# nodeBoard.net
KiCad netlist of a schematic drawn in EAGLE
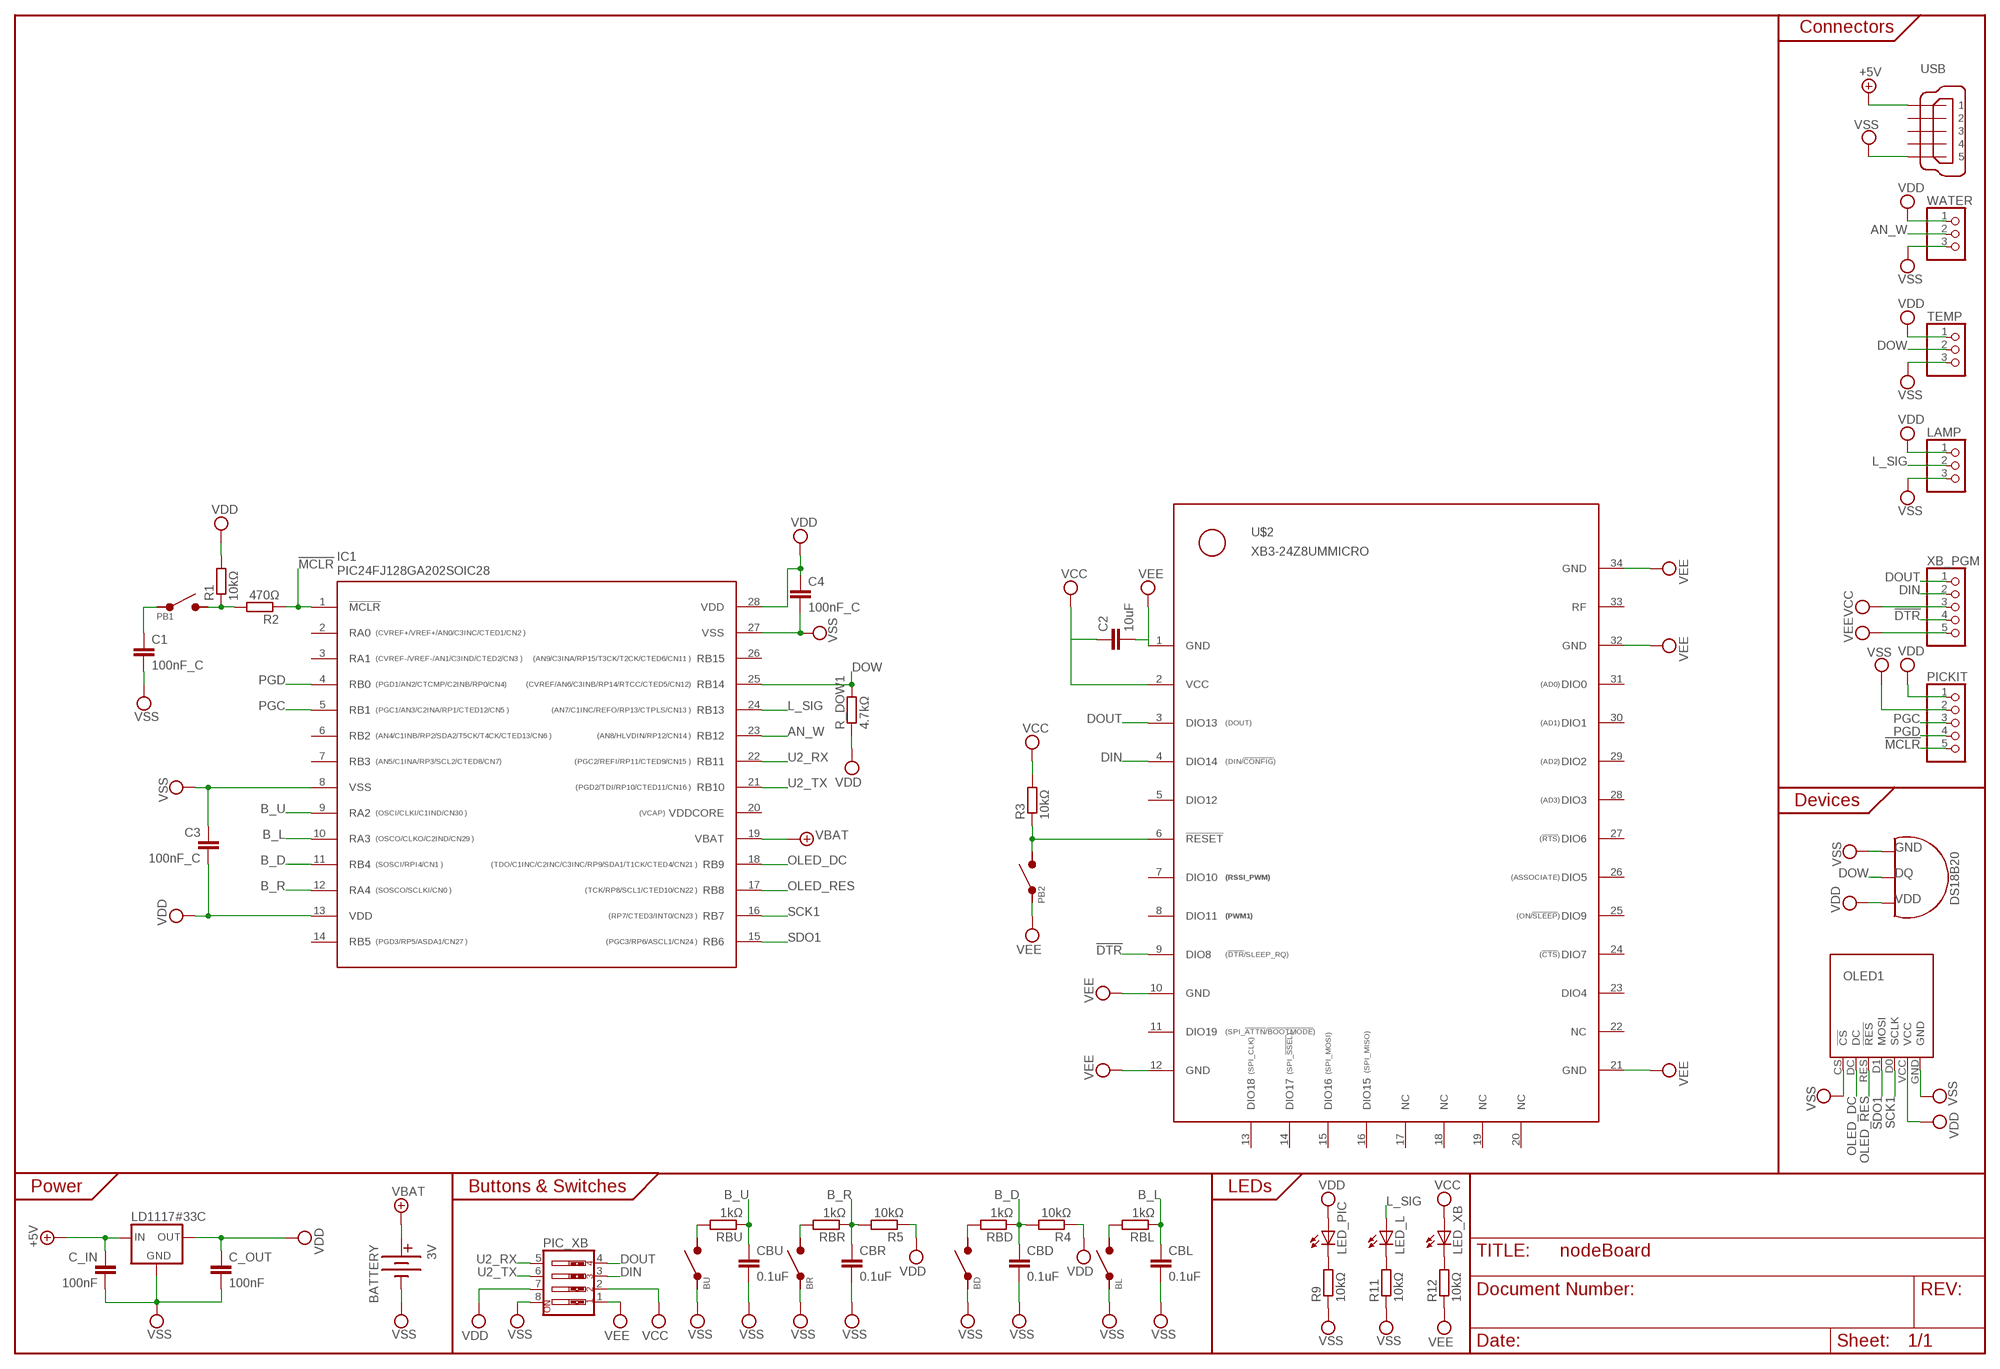
[diagram p0: schematic, sheet 1]

(export (version "E")
  (design (tool "Eeschema 10.0.6"))
  (components
    (comp (ref "3V")
      (value "BATTERY")
      (footprint "eagle-import:20MM_CELLHOLDER")
      (libsource (lib "eagle-import") (part "BATTERY"))
    )
    (comp (ref "BD")
      (value "PUSHBUTTON_4LEG_SMD")
      (footprint "eagle-import:TACTILE_SWITCH_SMD_6.2MM_BROWN")
      (libsource (lib "eagle-import") (part "PUSHBUTTON_4LEG_SMD"))
    )
    (comp (ref "BL")
      (value "PUSHBUTTON_4LEG_SMD")
      (footprint "eagle-import:TACTILE_SWITCH_SMD_6.2MM_BROWN")
      (libsource (lib "eagle-import") (part "PUSHBUTTON_4LEG_SMD"))
    )
    (comp (ref "BR")
      (value "PUSHBUTTON_4LEG_SMD")
      (footprint "eagle-import:TACTILE_SWITCH_SMD_6.2MM_BROWN")
      (libsource (lib "eagle-import") (part "PUSHBUTTON_4LEG_SMD"))
    )
    (comp (ref "BU")
      (value "PUSHBUTTON_4LEG_SMD")
      (footprint "eagle-import:TACTILE_SWITCH_SMD_6.2MM_BROWN")
      (libsource (lib "eagle-import") (part "PUSHBUTTON_4LEG_SMD"))
    )
    (comp (ref "C1")
      (value "100nF_C")
      (footprint "eagle-import:C0805")
      (libsource (lib "eagle-import") (part "C-EUC0805"))
    )
    (comp (ref "C2")
      (value "10uF")
      (footprint "eagle-import:C0805")
      (libsource (lib "eagle-import") (part "C-EUC0805"))
    )
    (comp (ref "C3")
      (value "100nF_C")
      (footprint "eagle-import:C0805")
      (libsource (lib "eagle-import") (part "C-EUC0805"))
    )
    (comp (ref "C4")
      (value "100nF_C")
      (footprint "eagle-import:C0805")
      (libsource (lib "eagle-import") (part "C-EUC0805"))
    )
    (comp (ref "CBD")
      (value "0.1uF")
      (footprint "eagle-import:C0805")
      (libsource (lib "eagle-import") (part "C-EUC0805"))
    )
    (comp (ref "CBL")
      (value "0.1uF")
      (footprint "eagle-import:C0805")
      (libsource (lib "eagle-import") (part "C-EUC0805"))
    )
    (comp (ref "CBR")
      (value "0.1uF")
      (footprint "eagle-import:C0805")
      (libsource (lib "eagle-import") (part "C-EUC0805"))
    )
    (comp (ref "CBU")
      (value "0.1uF")
      (footprint "eagle-import:C0805")
      (libsource (lib "eagle-import") (part "C-EUC0805"))
    )
    (comp (ref "C_IN")
      (value "100nF")
      (footprint "eagle-import:C0805")
      (libsource (lib "eagle-import") (part "C-EUC0805"))
    )
    (comp (ref "C_OUT")
      (value "100nF")
      (footprint "eagle-import:C0805")
      (libsource (lib "eagle-import") (part "C-EUC0805"))
    )
    (comp (ref "IC1")
      (value "PIC24FJ128GA202SOIC28")
      (footprint "eagle-import:SOIC28L")
      (libsource (lib "eagle-import") (part "PIC24FJ128GA202SOIC28"))
    )
    (comp (ref "LAMP")
      (value "PINHD-1X3")
      (footprint "eagle-import:1X03")
      (libsource (lib "eagle-import") (part "PINHD-1X3"))
    )
    (comp (ref "LED_L")
      (value "LEDCHIPLED_0805")
      (footprint "eagle-import:CHIPLED_0805")
      (libsource (lib "eagle-import") (part "LEDCHIPLED_0805"))
    )
    (comp (ref "LED_PIC")
      (value "LEDCHIPLED_0805")
      (footprint "eagle-import:CHIPLED_0805")
      (libsource (lib "eagle-import") (part "LEDCHIPLED_0805"))
    )
    (comp (ref "LED_XB")
      (value "LEDCHIPLED_0805")
      (footprint "eagle-import:CHIPLED_0805")
      (libsource (lib "eagle-import") (part "LEDCHIPLED_0805"))
    )
    (comp (ref "OLED1")
      (value "OLED_7PIN_SPI")
      (footprint "eagle-import:OLED_7PIN")
      (libsource (lib "eagle-import") (part "OLED_7PIN_SPI"))
    )
    (comp (ref "PB1")
      (value "PUSHBUTTON_2LEG")
      (footprint "eagle-import:PUSHBUTTON_6X3.5MM")
      (libsource (lib "eagle-import") (part "PUSHBUTTON_2LEG"))
    )
    (comp (ref "PB2")
      (value "PUSHBUTTON_2LEG")
      (footprint "eagle-import:PUSHBUTTON_6X3.5MM")
      (libsource (lib "eagle-import") (part "PUSHBUTTON_2LEG"))
    )
    (comp (ref "PICKIT")
      (value "PINHD-1X5")
      (footprint "eagle-import:1X05")
      (libsource (lib "eagle-import") (part "PINHD-1X5"))
    )
    (comp (ref "PIC_XB")
      (value "SW_DIP-4")
      (footprint "eagle-import:EDG-04")
      (libsource (lib "eagle-import") (part "SW_DIP-4"))
    )
    (comp (ref "R1")
      (value "10kΩ")
      (footprint "eagle-import:R0805")
      (libsource (lib "eagle-import") (part "R-EU_R0805"))
    )
    (comp (ref "R2")
      (value "470Ω")
      (footprint "eagle-import:R0805")
      (libsource (lib "eagle-import") (part "R-EU_R0805"))
    )
    (comp (ref "R3")
      (value "10kΩ")
      (footprint "eagle-import:R0805")
      (libsource (lib "eagle-import") (part "R-EU_R0805"))
    )
    (comp (ref "R4")
      (value "10kΩ")
      (footprint "eagle-import:R0805")
      (libsource (lib "eagle-import") (part "R-EU_R0805"))
    )
    (comp (ref "R5")
      (value "10kΩ")
      (footprint "eagle-import:R0805")
      (libsource (lib "eagle-import") (part "R-EU_R0805"))
    )
    (comp (ref "R9")
      (value "10kΩ")
      (footprint "eagle-import:R0805")
      (libsource (lib "eagle-import") (part "R-EU_R0805"))
    )
    (comp (ref "R11")
      (value "10kΩ")
      (footprint "eagle-import:R0805")
      (libsource (lib "eagle-import") (part "R-EU_R0805"))
    )
    (comp (ref "R12")
      (value "10kΩ")
      (footprint "eagle-import:R0805")
      (libsource (lib "eagle-import") (part "R-EU_R0805"))
    )
    (comp (ref "RBD")
      (value "1kΩ")
      (footprint "eagle-import:R0805")
      (libsource (lib "eagle-import") (part "R-EU_R0805"))
    )
    (comp (ref "RBL")
      (value "1kΩ")
      (footprint "eagle-import:R0805")
      (libsource (lib "eagle-import") (part "R-EU_R0805"))
    )
    (comp (ref "RBR")
      (value "1kΩ")
      (footprint "eagle-import:R0805")
      (libsource (lib "eagle-import") (part "R-EU_R0805"))
    )
    (comp (ref "RBU")
      (value "1kΩ")
      (footprint "eagle-import:R0805")
      (libsource (lib "eagle-import") (part "R-EU_R0805"))
    )
    (comp (ref "R_DOW1")
      (value "4.7kΩ")
      (footprint "eagle-import:R0805")
      (libsource (lib "eagle-import") (part "R-EU_R0805"))
    )
    (comp (ref "TEMP")
      (value "PINHD-1X3")
      (footprint "eagle-import:1X03")
      (libsource (lib "eagle-import") (part "PINHD-1X3"))
    )
    (comp (ref "U$1")
      (value "LD1117#33C")
      (footprint "eagle-import:DPACK")
      (libsource (lib "eagle-import") (part "LD1117#33C"))
    )
    (comp (ref "U$2")
      (value "XB3-24Z8UMMICRO")
      (footprint "eagle-import:XBEE3_MICRO")
      (libsource (lib "eagle-import") (part "XB3-24Z8UMMICRO"))
    )
    (comp (ref "U$7")
      (value "DS18B20")
      (footprint "eagle-import:TO92")
      (libsource (lib "eagle-import") (part "DS18B20"))
    )
    (comp (ref "USB")
      (value "MINI-USB-32005-201")
      (footprint "eagle-import:32005-201")
      (libsource (lib "eagle-import") (part "MINI-USB-32005-201"))
    )
    (comp (ref "WATER")
      (value "PINHD-1X3")
      (footprint "eagle-import:1X03")
      (libsource (lib "eagle-import") (part "PINHD-1X3"))
    )
    (comp (ref "XB_PGM")
      (value "PINHD-1X5")
      (footprint "eagle-import:1X05")
      (libsource (lib "eagle-import") (part "PINHD-1X5"))
    )
  )
  (nets
    (net (code "1") (name "+5V") (class "Default")
      (node (ref "C_IN") (pin "1") (pinfunction "1_1") (pintype "passive"))
      (node (ref "U$1") (pin "3") (pinfunction "IN_3") (pintype "power_in"))
      (node (ref "USB") (pin "1") (pinfunction "1_1") (pintype "passive"))
    )
    (net (code "2") (name "/AN_W") (class "Default")
      (node (ref "IC1") (pin "23") (pinfunction "RB12_23") (pintype "bidirectional"))
      (node (ref "WATER") (pin "2") (pinfunction "2_2") (pintype "passive"))
    )
    (net (code "3") (name "/B_D") (class "Default")
      (node (ref "CBD") (pin "1") (pinfunction "1_1") (pintype "passive"))
      (node (ref "IC1") (pin "11") (pinfunction "RB4_11") (pintype "bidirectional"))
      (node (ref "R4") (pin "2") (pinfunction "2_2") (pintype "passive"))
      (node (ref "RBD") (pin "1") (pinfunction "1_1") (pintype "passive"))
    )
    (net (code "4") (name "/B_L") (class "Default")
      (node (ref "CBL") (pin "1") (pinfunction "1_1") (pintype "passive"))
      (node (ref "IC1") (pin "10") (pinfunction "RA3_10") (pintype "bidirectional"))
      (node (ref "RBL") (pin "1") (pinfunction "1_1") (pintype "passive"))
    )
    (net (code "5") (name "/B_R") (class "Default")
      (node (ref "CBR") (pin "1") (pinfunction "1_1") (pintype "passive"))
      (node (ref "IC1") (pin "12") (pinfunction "RA4_12") (pintype "bidirectional"))
      (node (ref "R5") (pin "2") (pinfunction "2_2") (pintype "passive"))
      (node (ref "RBR") (pin "1") (pinfunction "1_1") (pintype "passive"))
    )
    (net (code "6") (name "/B_U") (class "Default")
      (node (ref "CBU") (pin "1") (pinfunction "1_1") (pintype "passive"))
      (node (ref "IC1") (pin "9") (pinfunction "RA2_9") (pintype "bidirectional"))
      (node (ref "RBU") (pin "1") (pinfunction "1_1") (pintype "passive"))
    )
    (net (code "7") (name "/DIN") (class "Default")
      (node (ref "PIC_XB") (pin "3") (pinfunction "3_3") (pintype "passive"))
      (node (ref "U$2") (pin "4") (pinfunction "DIO14_4") (pintype "bidirectional"))
      (node (ref "XB_PGM") (pin "2") (pinfunction "2_2") (pintype "passive"))
    )
    (net (code "8") (name "/DOUT") (class "Default")
      (node (ref "PIC_XB") (pin "4") (pinfunction "4_4") (pintype "passive"))
      (node (ref "U$2") (pin "3") (pinfunction "DIO13_3") (pintype "bidirectional"))
      (node (ref "XB_PGM") (pin "1") (pinfunction "1_1") (pintype "passive"))
    )
    (net (code "9") (name "/DOW") (class "Default")
      (node (ref "IC1") (pin "25") (pinfunction "RB14_25") (pintype "bidirectional"))
      (node (ref "R_DOW1") (pin "2") (pinfunction "2_2") (pintype "passive"))
      (node (ref "TEMP") (pin "2") (pinfunction "2_2") (pintype "passive"))
      (node (ref "U$7") (pin "2") (pinfunction "DQ_2") (pintype "bidirectional"))
    )
    (net (code "10") (name "/L_SIG") (class "Default")
      (node (ref "IC1") (pin "24") (pinfunction "RB13_24") (pintype "bidirectional"))
      (node (ref "LAMP") (pin "2") (pinfunction "2_2") (pintype "passive"))
      (node (ref "LED_L") (pin "A") (pinfunction "A_A") (pintype "passive"))
    )
    (net (code "11") (name "/OLED_DC") (class "Default")
      (node (ref "IC1") (pin "18") (pinfunction "RB9_18") (pintype "output"))
      (node (ref "OLED1") (pin "DC") (pinfunction "DC_DC") (pintype "bidirectional"))
    )
    (net (code "12") (name "/OLED_RES") (class "Default")
      (node (ref "IC1") (pin "17") (pinfunction "RB8_17") (pintype "input"))
      (node (ref "OLED1") (pin "RES") (pinfunction "~{RES}_RES") (pintype "bidirectional"))
    )
    (net (code "13") (name "/PGC") (class "Default")
      (node (ref "IC1") (pin "5") (pinfunction "RB1_5") (pintype "bidirectional"))
      (node (ref "PICKIT") (pin "3") (pinfunction "3_3") (pintype "passive"))
    )
    (net (code "14") (name "/PGD") (class "Default")
      (node (ref "IC1") (pin "4") (pinfunction "RB0_4") (pintype "bidirectional"))
      (node (ref "PICKIT") (pin "4") (pinfunction "4_4") (pintype "passive"))
    )
    (net (code "15") (name "/SCK1") (class "Default")
      (node (ref "IC1") (pin "16") (pinfunction "RB7_16") (pintype "bidirectional"))
      (node (ref "OLED1") (pin "D0") (pinfunction "SCLK_D0") (pintype "bidirectional"))
    )
    (net (code "16") (name "/SDO1") (class "Default")
      (node (ref "IC1") (pin "15") (pinfunction "RB6_15") (pintype "bidirectional"))
      (node (ref "OLED1") (pin "D1") (pinfunction "MOSI_D1") (pintype "bidirectional"))
    )
    (net (code "17") (name "/U2_RX") (class "Default")
      (node (ref "IC1") (pin "22") (pinfunction "RB11_22") (pintype "input"))
      (node (ref "PIC_XB") (pin "5") (pinfunction "5_5") (pintype "passive"))
    )
    (net (code "18") (name "/U2_TX") (class "Default")
      (node (ref "IC1") (pin "21") (pinfunction "RB10_21") (pintype "input"))
      (node (ref "PIC_XB") (pin "6") (pinfunction "6_6") (pintype "passive"))
    )
    (net (code "19") (name "/VDDCORE") (class "Default")
      (node (ref "IC1") (pin "20") (pinfunction "VDDCORE_20") (pintype "power_in"))
    )
    (net (code "20") (name "/~{DTR}") (class "Default")
      (node (ref "U$2") (pin "9") (pinfunction "DIO8_9") (pintype "bidirectional"))
      (node (ref "XB_PGM") (pin "4") (pinfunction "4_4") (pintype "passive"))
    )
    (net (code "21") (name "/~{MCLR}") (class "Default")
      (node (ref "IC1") (pin "1") (pinfunction "~{MCLR}_1") (pintype "bidirectional"))
      (node (ref "PICKIT") (pin "5") (pinfunction "5_5") (pintype "passive"))
      (node (ref "R2") (pin "1") (pinfunction "1_1") (pintype "passive"))
    )
    (net (code "22") (name "Net-(BD-P$2-PadB1)") (class "Default")
      (node (ref "BD") (pin "B1") (pinfunction "P$2_B1") (pintype "bidirectional"))
      (node (ref "BD") (pin "B2") (pinfunction "P$2_B2") (pintype "bidirectional"))
      (node (ref "RBD") (pin "2") (pinfunction "2_2") (pintype "passive"))
    )
    (net (code "23") (name "Net-(BL-P$2-PadB1)") (class "Default")
      (node (ref "BL") (pin "B1") (pinfunction "P$2_B1") (pintype "bidirectional"))
      (node (ref "BL") (pin "B2") (pinfunction "P$2_B2") (pintype "bidirectional"))
      (node (ref "RBL") (pin "2") (pinfunction "2_2") (pintype "passive"))
    )
    (net (code "24") (name "Net-(BR-P$2-PadB1)") (class "Default")
      (node (ref "BR") (pin "B1") (pinfunction "P$2_B1") (pintype "bidirectional"))
      (node (ref "BR") (pin "B2") (pinfunction "P$2_B2") (pintype "bidirectional"))
      (node (ref "RBR") (pin "2") (pinfunction "2_2") (pintype "passive"))
    )
    (net (code "25") (name "Net-(BU-P$2-PadB1)") (class "Default")
      (node (ref "BU") (pin "B1") (pinfunction "P$2_B1") (pintype "bidirectional"))
      (node (ref "BU") (pin "B2") (pinfunction "P$2_B2") (pintype "bidirectional"))
      (node (ref "RBU") (pin "2") (pinfunction "2_2") (pintype "passive"))
    )
    (net (code "26") (name "Net-(C1-Pad1)") (class "Default")
      (node (ref "C1") (pin "1") (pinfunction "1_1") (pintype "passive"))
      (node (ref "PB1") (pin "P$1") (pinfunction "P$1_P$1") (pintype "bidirectional"))
    )
    (net (code "27") (name "Net-(LED_L-PadC)") (class "Default")
      (node (ref "LED_L") (pin "C") (pinfunction "C_C") (pintype "passive"))
      (node (ref "R11") (pin "2") (pinfunction "2_2") (pintype "passive"))
    )
    (net (code "28") (name "Net-(LED_PIC-PadC)") (class "Default")
      (node (ref "LED_PIC") (pin "C") (pinfunction "C_C") (pintype "passive"))
      (node (ref "R9") (pin "2") (pinfunction "2_2") (pintype "passive"))
    )
    (net (code "29") (name "Net-(LED_XB-PadC)") (class "Default")
      (node (ref "LED_XB") (pin "C") (pinfunction "C_C") (pintype "passive"))
      (node (ref "R12") (pin "2") (pinfunction "2_2") (pintype "passive"))
    )
    (net (code "30") (name "Net-(PB1-PadP$2)") (class "Default")
      (node (ref "PB1") (pin "P$2") (pinfunction "P$2_P$2") (pintype "bidirectional"))
      (node (ref "R1") (pin "1") (pinfunction "1_1") (pintype "passive"))
      (node (ref "R2") (pin "2") (pinfunction "2_2") (pintype "passive"))
    )
    (net (code "31") (name "Net-(U$2-~{RESET})") (class "Default")
      (node (ref "PB2") (pin "P$2") (pinfunction "P$2_P$2") (pintype "bidirectional"))
      (node (ref "R3") (pin "1") (pinfunction "1_1") (pintype "passive"))
      (node (ref "U$2") (pin "6") (pinfunction "~{RESET}_6") (pintype "input"))
    )
    (net (code "32") (name "VBAT") (class "Default")
      (node (ref "3V") (pin "+@1") (pinfunction "+_+@1") (pintype "power_in"))
      (node (ref "3V") (pin "+@2") (pinfunction "+_+@2") (pintype "power_in"))
      (node (ref "IC1") (pin "19") (pinfunction "VBAT_19") (pintype "passive"))
    )
    (net (code "33") (name "VCC") (class "Default")
      (node (ref "C2") (pin "1") (pinfunction "1_1") (pintype "passive"))
      (node (ref "LED_XB") (pin "A") (pinfunction "A_A") (pintype "passive"))
      (node (ref "PIC_XB") (pin "2") (pinfunction "2_2") (pintype "passive"))
      (node (ref "R3") (pin "2") (pinfunction "2_2") (pintype "passive"))
      (node (ref "U$2") (pin "2") (pinfunction "VCC_2") (pintype "power_in"))
      (node (ref "XB_PGM") (pin "3") (pinfunction "3_3") (pintype "passive"))
    )
    (net (code "34") (name "VDD") (class "Default")
      (node (ref "C3") (pin "2") (pinfunction "2_2") (pintype "passive"))
      (node (ref "C4") (pin "1") (pinfunction "1_1") (pintype "passive"))
      (node (ref "C_OUT") (pin "1") (pinfunction "1_1") (pintype "passive"))
      (node (ref "IC1") (pin "13") (pinfunction "VDD_13") (pintype "power_in"))
      (node (ref "IC1") (pin "28") (pinfunction "VDD_28") (pintype "power_in"))
      (node (ref "LAMP") (pin "1") (pinfunction "1_1") (pintype "passive"))
      (node (ref "LED_PIC") (pin "A") (pinfunction "A_A") (pintype "passive"))
      (node (ref "OLED1") (pin "VCC") (pinfunction "VCC_VCC") (pintype "bidirectional"))
      (node (ref "PICKIT") (pin "1") (pinfunction "1_1") (pintype "passive"))
      (node (ref "PIC_XB") (pin "7") (pinfunction "7_7") (pintype "passive"))
      (node (ref "R1") (pin "2") (pinfunction "2_2") (pintype "passive"))
      (node (ref "R4") (pin "1") (pinfunction "1_1") (pintype "passive"))
      (node (ref "R5") (pin "1") (pinfunction "1_1") (pintype "passive"))
      (node (ref "R_DOW1") (pin "1") (pinfunction "1_1") (pintype "passive"))
      (node (ref "TEMP") (pin "1") (pinfunction "1_1") (pintype "passive"))
      (node (ref "U$1") (pin "2") (pinfunction "OUT_2") (pintype "power_in"))
      (node (ref "U$7") (pin "3") (pinfunction "VDD_3") (pintype "power_in"))
      (node (ref "WATER") (pin "1") (pinfunction "1_1") (pintype "passive"))
    )
    (net (code "35") (name "VEE") (class "Default")
      (node (ref "C2") (pin "2") (pinfunction "2_2") (pintype "passive"))
      (node (ref "PB2") (pin "P$1") (pinfunction "P$1_P$1") (pintype "bidirectional"))
      (node (ref "PIC_XB") (pin "1") (pinfunction "1_1") (pintype "passive"))
      (node (ref "R12") (pin "1") (pinfunction "1_1") (pintype "passive"))
      (node (ref "U$2") (pin "1") (pinfunction "GND_1") (pintype "power_in"))
      (node (ref "U$2") (pin "10") (pinfunction "GND_10") (pintype "power_in"))
      (node (ref "U$2") (pin "12") (pinfunction "GND_12") (pintype "power_in"))
      (node (ref "U$2") (pin "21") (pinfunction "GND_21") (pintype "power_in"))
      (node (ref "U$2") (pin "32") (pinfunction "GND_32") (pintype "power_in"))
      (node (ref "U$2") (pin "34") (pinfunction "GND_34") (pintype "power_in"))
      (node (ref "XB_PGM") (pin "5") (pinfunction "5_5") (pintype "passive"))
    )
    (net (code "36") (name "VSS") (class "Default")
      (node (ref "3V") (pin "-") (pinfunction "-_-") (pintype "power_in"))
      (node (ref "BD") (pin "A1") (pinfunction "P$1_A1") (pintype "bidirectional"))
      (node (ref "BD") (pin "A2") (pinfunction "P$1_A2") (pintype "bidirectional"))
      (node (ref "BL") (pin "A1") (pinfunction "P$1_A1") (pintype "bidirectional"))
      (node (ref "BL") (pin "A2") (pinfunction "P$1_A2") (pintype "bidirectional"))
      (node (ref "BR") (pin "A1") (pinfunction "P$1_A1") (pintype "bidirectional"))
      (node (ref "BR") (pin "A2") (pinfunction "P$1_A2") (pintype "bidirectional"))
      (node (ref "BU") (pin "A1") (pinfunction "P$1_A1") (pintype "bidirectional"))
      (node (ref "BU") (pin "A2") (pinfunction "P$1_A2") (pintype "bidirectional"))
      (node (ref "C1") (pin "2") (pinfunction "2_2") (pintype "passive"))
      (node (ref "C3") (pin "1") (pinfunction "1_1") (pintype "passive"))
      (node (ref "C4") (pin "2") (pinfunction "2_2") (pintype "passive"))
      (node (ref "CBD") (pin "2") (pinfunction "2_2") (pintype "passive"))
      (node (ref "CBL") (pin "2") (pinfunction "2_2") (pintype "passive"))
      (node (ref "CBR") (pin "2") (pinfunction "2_2") (pintype "passive"))
      (node (ref "CBU") (pin "2") (pinfunction "2_2") (pintype "passive"))
      (node (ref "C_IN") (pin "2") (pinfunction "2_2") (pintype "passive"))
      (node (ref "C_OUT") (pin "2") (pinfunction "2_2") (pintype "passive"))
      (node (ref "IC1") (pin "27") (pinfunction "VSS_27") (pintype "power_in"))
      (node (ref "IC1") (pin "8") (pinfunction "VSS_8") (pintype "power_in"))
      (node (ref "LAMP") (pin "3") (pinfunction "3_3") (pintype "passive"))
      (node (ref "OLED1") (pin "CS") (pinfunction "~{CS}_CS") (pintype "bidirectional"))
      (node (ref "OLED1") (pin "GND") (pinfunction "GND_GND") (pintype "bidirectional"))
      (node (ref "PICKIT") (pin "2") (pinfunction "2_2") (pintype "passive"))
      (node (ref "PIC_XB") (pin "8") (pinfunction "8_8") (pintype "passive"))
      (node (ref "R11") (pin "1") (pinfunction "1_1") (pintype "passive"))
      (node (ref "R9") (pin "1") (pinfunction "1_1") (pintype "passive"))
      (node (ref "TEMP") (pin "3") (pinfunction "3_3") (pintype "passive"))
      (node (ref "U$1") (pin "1") (pinfunction "GND_1") (pintype "power_in"))
      (node (ref "U$7") (pin "1") (pinfunction "GND_1") (pintype "power_in"))
      (node (ref "USB") (pin "5") (pinfunction "5_5") (pintype "passive"))
      (node (ref "WATER") (pin "3") (pinfunction "3_3") (pintype "passive"))
    )
    (net (code "37") (name "unconnected-(IC1-RA0-Pad2)") (class "Default")
      (node (ref "IC1") (pin "2") (pinfunction "RA0_2") (pintype "bidirectional"))
    )
    (net (code "38") (name "unconnected-(IC1-RA1-Pad3)") (class "Default")
      (node (ref "IC1") (pin "3") (pinfunction "RA1_3") (pintype "bidirectional"))
    )
    (net (code "39") (name "unconnected-(IC1-RB2-Pad6)") (class "Default")
      (node (ref "IC1") (pin "6") (pinfunction "RB2_6") (pintype "bidirectional"))
    )
    (net (code "40") (name "unconnected-(IC1-RB3-Pad7)") (class "Default")
      (node (ref "IC1") (pin "7") (pinfunction "RB3_7") (pintype "bidirectional"))
    )
    (net (code "41") (name "unconnected-(IC1-RB5-Pad14)") (class "Default")
      (node (ref "IC1") (pin "14") (pinfunction "RB5_14") (pintype "bidirectional"))
    )
    (net (code "42") (name "unconnected-(IC1-RB15-Pad26)") (class "Default")
      (node (ref "IC1") (pin "26") (pinfunction "RB15_26") (pintype "bidirectional"))
    )
    (net (code "43") (name "unconnected-(U$2-DIO0-Pad31)") (class "Default")
      (node (ref "U$2") (pin "31") (pinfunction "DIO0_31") (pintype "bidirectional"))
    )
    (net (code "44") (name "unconnected-(U$2-DIO1-Pad30)") (class "Default")
      (node (ref "U$2") (pin "30") (pinfunction "DIO1_30") (pintype "bidirectional"))
    )
    (net (code "45") (name "unconnected-(U$2-DIO2-Pad29)") (class "Default")
      (node (ref "U$2") (pin "29") (pinfunction "DIO2_29") (pintype "bidirectional"))
    )
    (net (code "46") (name "unconnected-(U$2-DIO3-Pad28)") (class "Default")
      (node (ref "U$2") (pin "28") (pinfunction "DIO3_28") (pintype "bidirectional"))
    )
    (net (code "47") (name "unconnected-(U$2-DIO4-Pad23)") (class "Default")
      (node (ref "U$2") (pin "23") (pinfunction "DIO4_23") (pintype "bidirectional"))
    )
    (net (code "48") (name "unconnected-(U$2-DIO5-Pad26)") (class "Default")
      (node (ref "U$2") (pin "26") (pinfunction "DIO5_26") (pintype "bidirectional"))
    )
    (net (code "49") (name "unconnected-(U$2-DIO6-Pad27)") (class "Default")
      (node (ref "U$2") (pin "27") (pinfunction "DIO6_27") (pintype "bidirectional"))
    )
    (net (code "50") (name "unconnected-(U$2-DIO7-Pad24)") (class "Default")
      (node (ref "U$2") (pin "24") (pinfunction "DIO7_24") (pintype "bidirectional"))
    )
    (net (code "51") (name "unconnected-(U$2-DIO9-Pad25)") (class "Default")
      (node (ref "U$2") (pin "25") (pinfunction "DIO9_25") (pintype "bidirectional"))
    )
    (net (code "52") (name "unconnected-(U$2-DIO10-Pad7)") (class "Default")
      (node (ref "U$2") (pin "7") (pinfunction "DIO10_7") (pintype "bidirectional"))
    )
    (net (code "53") (name "unconnected-(U$2-DIO11-Pad8)") (class "Default")
      (node (ref "U$2") (pin "8") (pinfunction "DIO11_8") (pintype "bidirectional"))
    )
    (net (code "54") (name "unconnected-(U$2-DIO12-Pad5)") (class "Default")
      (node (ref "U$2") (pin "5") (pinfunction "DIO12_5") (pintype "bidirectional"))
    )
    (net (code "55") (name "unconnected-(U$2-DIO15-Pad16)") (class "Default")
      (node (ref "U$2") (pin "16") (pinfunction "DIO15_16") (pintype "output"))
    )
    (net (code "56") (name "unconnected-(U$2-DIO16-Pad15)") (class "Default")
      (node (ref "U$2") (pin "15") (pinfunction "DIO16_15") (pintype "input"))
    )
    (net (code "57") (name "unconnected-(U$2-DIO17-Pad14)") (class "Default")
      (node (ref "U$2") (pin "14") (pinfunction "DIO17_14") (pintype "input"))
    )
    (net (code "58") (name "unconnected-(U$2-DIO18-Pad13)") (class "Default")
      (node (ref "U$2") (pin "13") (pinfunction "DIO18_13") (pintype "input"))
    )
    (net (code "59") (name "unconnected-(U$2-DIO19-Pad11)") (class "Default")
      (node (ref "U$2") (pin "11") (pinfunction "DIO19_11") (pintype "output"))
    )
    (net (code "60") (name "unconnected-(U$2-NC-Pad17)") (class "Default")
      (node (ref "U$2") (pin "17") (pinfunction "NC_17") (pintype "no_connect"))
    )
    (net (code "61") (name "unconnected-(U$2-NC-Pad18)") (class "Default")
      (node (ref "U$2") (pin "18") (pinfunction "NC_18") (pintype "no_connect"))
    )
    (net (code "62") (name "unconnected-(U$2-NC-Pad19)") (class "Default")
      (node (ref "U$2") (pin "19") (pinfunction "NC_19") (pintype "no_connect"))
    )
    (net (code "63") (name "unconnected-(U$2-NC-Pad20)") (class "Default")
      (node (ref "U$2") (pin "20") (pinfunction "NC_20") (pintype "no_connect"))
    )
    (net (code "64") (name "unconnected-(U$2-NC-Pad22)") (class "Default")
      (node (ref "U$2") (pin "22") (pinfunction "NC_22") (pintype "no_connect"))
    )
    (net (code "65") (name "unconnected-(U$2-RF-Pad33)") (class "Default")
      (node (ref "U$2") (pin "33") (pinfunction "RF_33") (pintype "bidirectional"))
    )
    (net (code "66") (name "unconnected-(USB-Pad2)") (class "Default")
      (node (ref "USB") (pin "2") (pinfunction "2_2") (pintype "passive"))
    )
    (net (code "67") (name "unconnected-(USB-Pad3)") (class "Default")
      (node (ref "USB") (pin "3") (pinfunction "3_3") (pintype "passive"))
    )
    (net (code "68") (name "unconnected-(USB-Pad4)") (class "Default")
      (node (ref "USB") (pin "4") (pinfunction "4_4") (pintype "passive"))
    )
  )
)
